# Wireless.net
KiCad netlist of a schematic drawn in Altium Designer
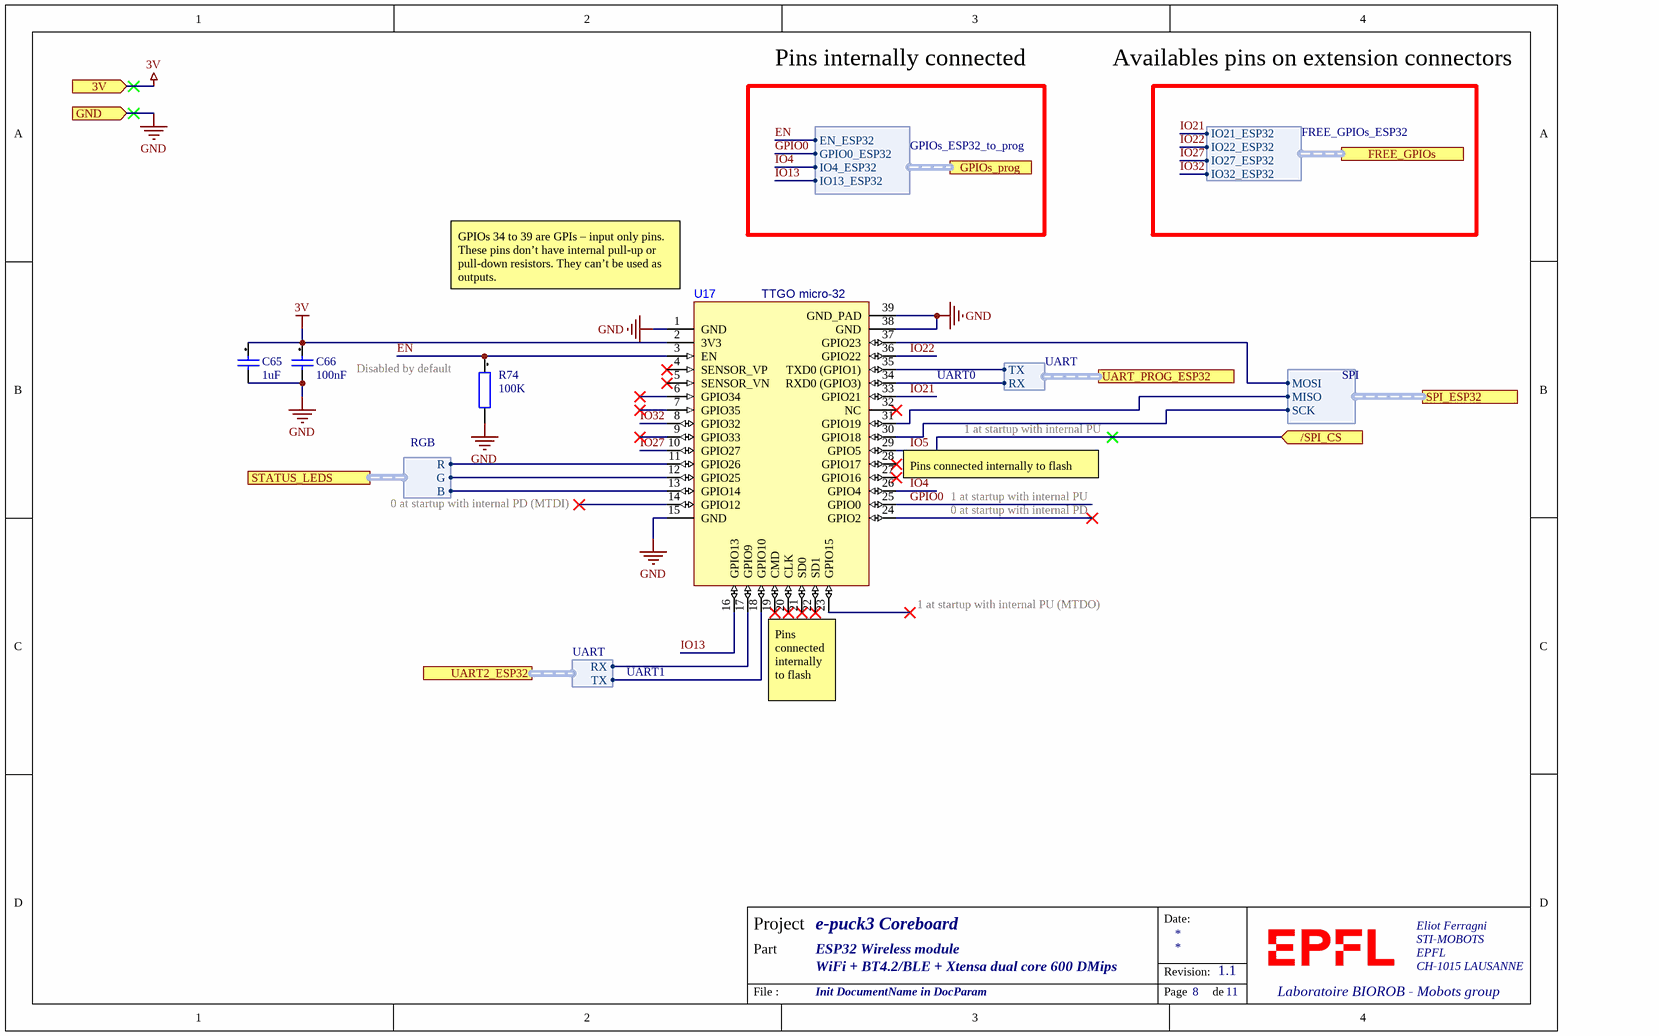
[diagram p0: Wireless.SchDoc]

(export (version "E")
  (design (tool "Eeschema 10.0.6"))
  (components
    (comp (ref "C65")
      (value "1uF")
      (footprint "CAPC0201(0603)33_L")
      (description "Capacitor 0201")
      (libsource (lib "LSRO1Altium") (part "CAP-NP"))
    )
    (comp (ref "C66")
      (value "100nF")
      (footprint "CAPC0201(0603)33_L")
      (description "Capacitor 0201")
      (libsource (lib "LSRO1Altium") (part "CAP-NP"))
    )
    (comp (ref "R74")
      (value "100K")
      (footprint "RESC0201(0603)_L")
      (description "Resistor 0201")
      (libsource (lib "LSRO1Altium") (part "RES"))
    )
    (comp (ref "U17")
      (value "TTGO micro-32 (ESP32)")
      (footprint "TTGO Micro-32 (ESP32)")
      (description "Wi-Fi BT BLE MCU Module")
      (fields (field (name "MANUFACTURER") "LilyLGo") (field (name "PART NUMBER") "TTGO micro-32"))
      (libsource (lib "Schlib") (part "TTGO micro-32 (ESP32)"))
    )
  )
  (nets
    (net (code "6") (name "/B") (class "Default")
      (node (ref "U17") (pin "13") (pinfunction "GPIO14_13") (pintype "bidirectional"))
    )
    (net (code "7") (name "/EN") (class "Default")
      (node (ref "R74") (pin "1") (pinfunction "1_1") (pintype "passive"))
      (node (ref "U17") (pin "3") (pinfunction "EN_3") (pintype "input"))
    )
    (net (code "8") (name "/G") (class "Default")
      (node (ref "U17") (pin "12") (pinfunction "GPIO25_12") (pintype "bidirectional"))
    )
    (net (code "9") (name "/GPIO0") (class "Default")
      (node (ref "U17") (pin "25") (pinfunction "GPIO0_25") (pintype "bidirectional"))
    )
    (net (code "10") (name "/IO4") (class "Default")
      (node (ref "U17") (pin "26") (pinfunction "GPIO4_26") (pintype "bidirectional"))
    )
    (net (code "11") (name "/IO5") (class "Default")
      (node (ref "U17") (pin "29") (pinfunction "GPIO5_29") (pintype "bidirectional"))
    )
    (net (code "12") (name "/IO13") (class "Default")
      (node (ref "U17") (pin "16") (pinfunction "GPIO13_16") (pintype "bidirectional"))
    )
    (net (code "13") (name "/IO21") (class "Default")
      (node (ref "U17") (pin "33") (pinfunction "GPIO21_33") (pintype "bidirectional"))
    )
    (net (code "14") (name "/IO22") (class "Default")
      (node (ref "U17") (pin "36") (pinfunction "GPIO22_36") (pintype "bidirectional"))
    )
    (net (code "15") (name "/IO27") (class "Default")
      (node (ref "U17") (pin "10") (pinfunction "GPIO27_10") (pintype "bidirectional"))
    )
    (net (code "16") (name "/IO32") (class "Default")
      (node (ref "U17") (pin "8") (pinfunction "GPIO32_8") (pintype "bidirectional"))
    )
    (net (code "17") (name "/MISO") (class "Default")
      (node (ref "U17") (pin "31") (pinfunction "GPIO19_31") (pintype "bidirectional"))
    )
    (net (code "18") (name "/MOSI") (class "Default")
      (node (ref "U17") (pin "37") (pinfunction "GPIO23_37") (pintype "bidirectional"))
    )
    (net (code "19") (name "/R") (class "Default")
      (node (ref "U17") (pin "11") (pinfunction "GPIO26_11") (pintype "bidirectional"))
    )
    (net (code "20") (name "/SCK") (class "Default")
      (node (ref "U17") (pin "30") (pinfunction "GPIO18_30") (pintype "bidirectional"))
    )
    (net (code "26") (name "3V") (class "Default")
      (node (ref "C65") (pin "1") (pinfunction "1_1") (pintype "passive"))
      (node (ref "C66") (pin "1") (pinfunction "1_1") (pintype "passive"))
      (node (ref "U17") (pin "2") (pinfunction "3V3_2") (pintype "power_in"))
    )
    (net (code "27") (name "GND") (class "Default")
      (node (ref "C65") (pin "2") (pinfunction "2_2") (pintype "passive"))
      (node (ref "C66") (pin "2") (pinfunction "2_2") (pintype "passive"))
      (node (ref "R74") (pin "2") (pinfunction "2_2") (pintype "passive"))
      (node (ref "U17") (pin "1") (pinfunction "GND_1") (pintype "power_in"))
      (node (ref "U17") (pin "15") (pinfunction "GND_15") (pintype "power_in"))
      (node (ref "U17") (pin "38") (pinfunction "GND_38") (pintype "power_in"))
      (node (ref "U17") (pin "39") (pinfunction "GND_PAD_39") (pintype "power_in"))
    )
    (net (code "28") (name "unconnected-(U17-CLK-Pad20)") (class "Default")
      (node (ref "U17") (pin "20") (pinfunction "CLK_20") (pintype "bidirectional+no_connect"))
    )
    (net (code "29") (name "unconnected-(U17-CMD-Pad19)") (class "Default")
      (node (ref "U17") (pin "19") (pinfunction "CMD_19") (pintype "bidirectional+no_connect"))
    )
    (net (code "30") (name "unconnected-(U17-GPIO2-Pad24)") (class "Default")
      (node (ref "U17") (pin "24") (pinfunction "GPIO2_24") (pintype "bidirectional+no_connect"))
    )
    (net (code "31") (name "unconnected-(U17-GPIO9-Pad17)") (class "Default")
      (node (ref "U17") (pin "17") (pinfunction "GPIO9_17") (pintype "bidirectional"))
    )
    (net (code "32") (name "unconnected-(U17-GPIO10-Pad18)") (class "Default")
      (node (ref "U17") (pin "18") (pinfunction "GPIO10_18") (pintype "bidirectional"))
    )
    (net (code "33") (name "unconnected-(U17-GPIO12-Pad14)") (class "Default")
      (node (ref "U17") (pin "14") (pinfunction "GPIO12_14") (pintype "bidirectional+no_connect"))
    )
    (net (code "34") (name "unconnected-(U17-GPIO15-Pad23)") (class "Default")
      (node (ref "U17") (pin "23") (pinfunction "GPIO15_23") (pintype "bidirectional+no_connect"))
    )
    (net (code "35") (name "unconnected-(U17-GPIO16-Pad27)") (class "Default")
      (node (ref "U17") (pin "27") (pinfunction "GPIO16_27") (pintype "bidirectional+no_connect"))
    )
    (net (code "36") (name "unconnected-(U17-GPIO17-Pad28)") (class "Default")
      (node (ref "U17") (pin "28") (pinfunction "GPIO17_28") (pintype "bidirectional+no_connect"))
    )
    (net (code "37") (name "unconnected-(U17-GPIO33-Pad9)") (class "Default")
      (node (ref "U17") (pin "9") (pinfunction "GPIO33_9") (pintype "bidirectional+no_connect"))
    )
    (net (code "38") (name "unconnected-(U17-GPIO34-Pad6)") (class "Default")
      (node (ref "U17") (pin "6") (pinfunction "GPIO34_6") (pintype "input+no_connect"))
    )
    (net (code "39") (name "unconnected-(U17-GPIO35-Pad7)") (class "Default")
      (node (ref "U17") (pin "7") (pinfunction "GPIO35_7") (pintype "input+no_connect"))
    )
    (net (code "40") (name "unconnected-(U17-NC-Pad32)") (class "Default")
      (node (ref "U17") (pin "32") (pinfunction "NC_32") (pintype "passive+no_connect"))
    )
    (net (code "41") (name "unconnected-(U17-RXD0_(GPIO3)-Pad34)") (class "Default")
      (node (ref "U17") (pin "34") (pinfunction "RXD0_(GPIO3)_34") (pintype "bidirectional"))
    )
    (net (code "42") (name "unconnected-(U17-SD0-Pad21)") (class "Default")
      (node (ref "U17") (pin "21") (pinfunction "SD0_21") (pintype "bidirectional+no_connect"))
    )
    (net (code "43") (name "unconnected-(U17-SD1-Pad22)") (class "Default")
      (node (ref "U17") (pin "22") (pinfunction "SD1_22") (pintype "bidirectional+no_connect"))
    )
    (net (code "44") (name "unconnected-(U17-SENSOR_VN-Pad5)") (class "Default")
      (node (ref "U17") (pin "5") (pinfunction "SENSOR_VN_5") (pintype "input+no_connect"))
    )
    (net (code "45") (name "unconnected-(U17-SENSOR_VP-Pad4)") (class "Default")
      (node (ref "U17") (pin "4") (pinfunction "SENSOR_VP_4") (pintype "input+no_connect"))
    )
    (net (code "46") (name "unconnected-(U17-TXD0_(GPIO1)-Pad35)") (class "Default")
      (node (ref "U17") (pin "35") (pinfunction "TXD0_(GPIO1)_35") (pintype "bidirectional"))
    )
  )
)
